# Octaplexerv6.net
KiCad netlist of a schematic drawn in EAGLE
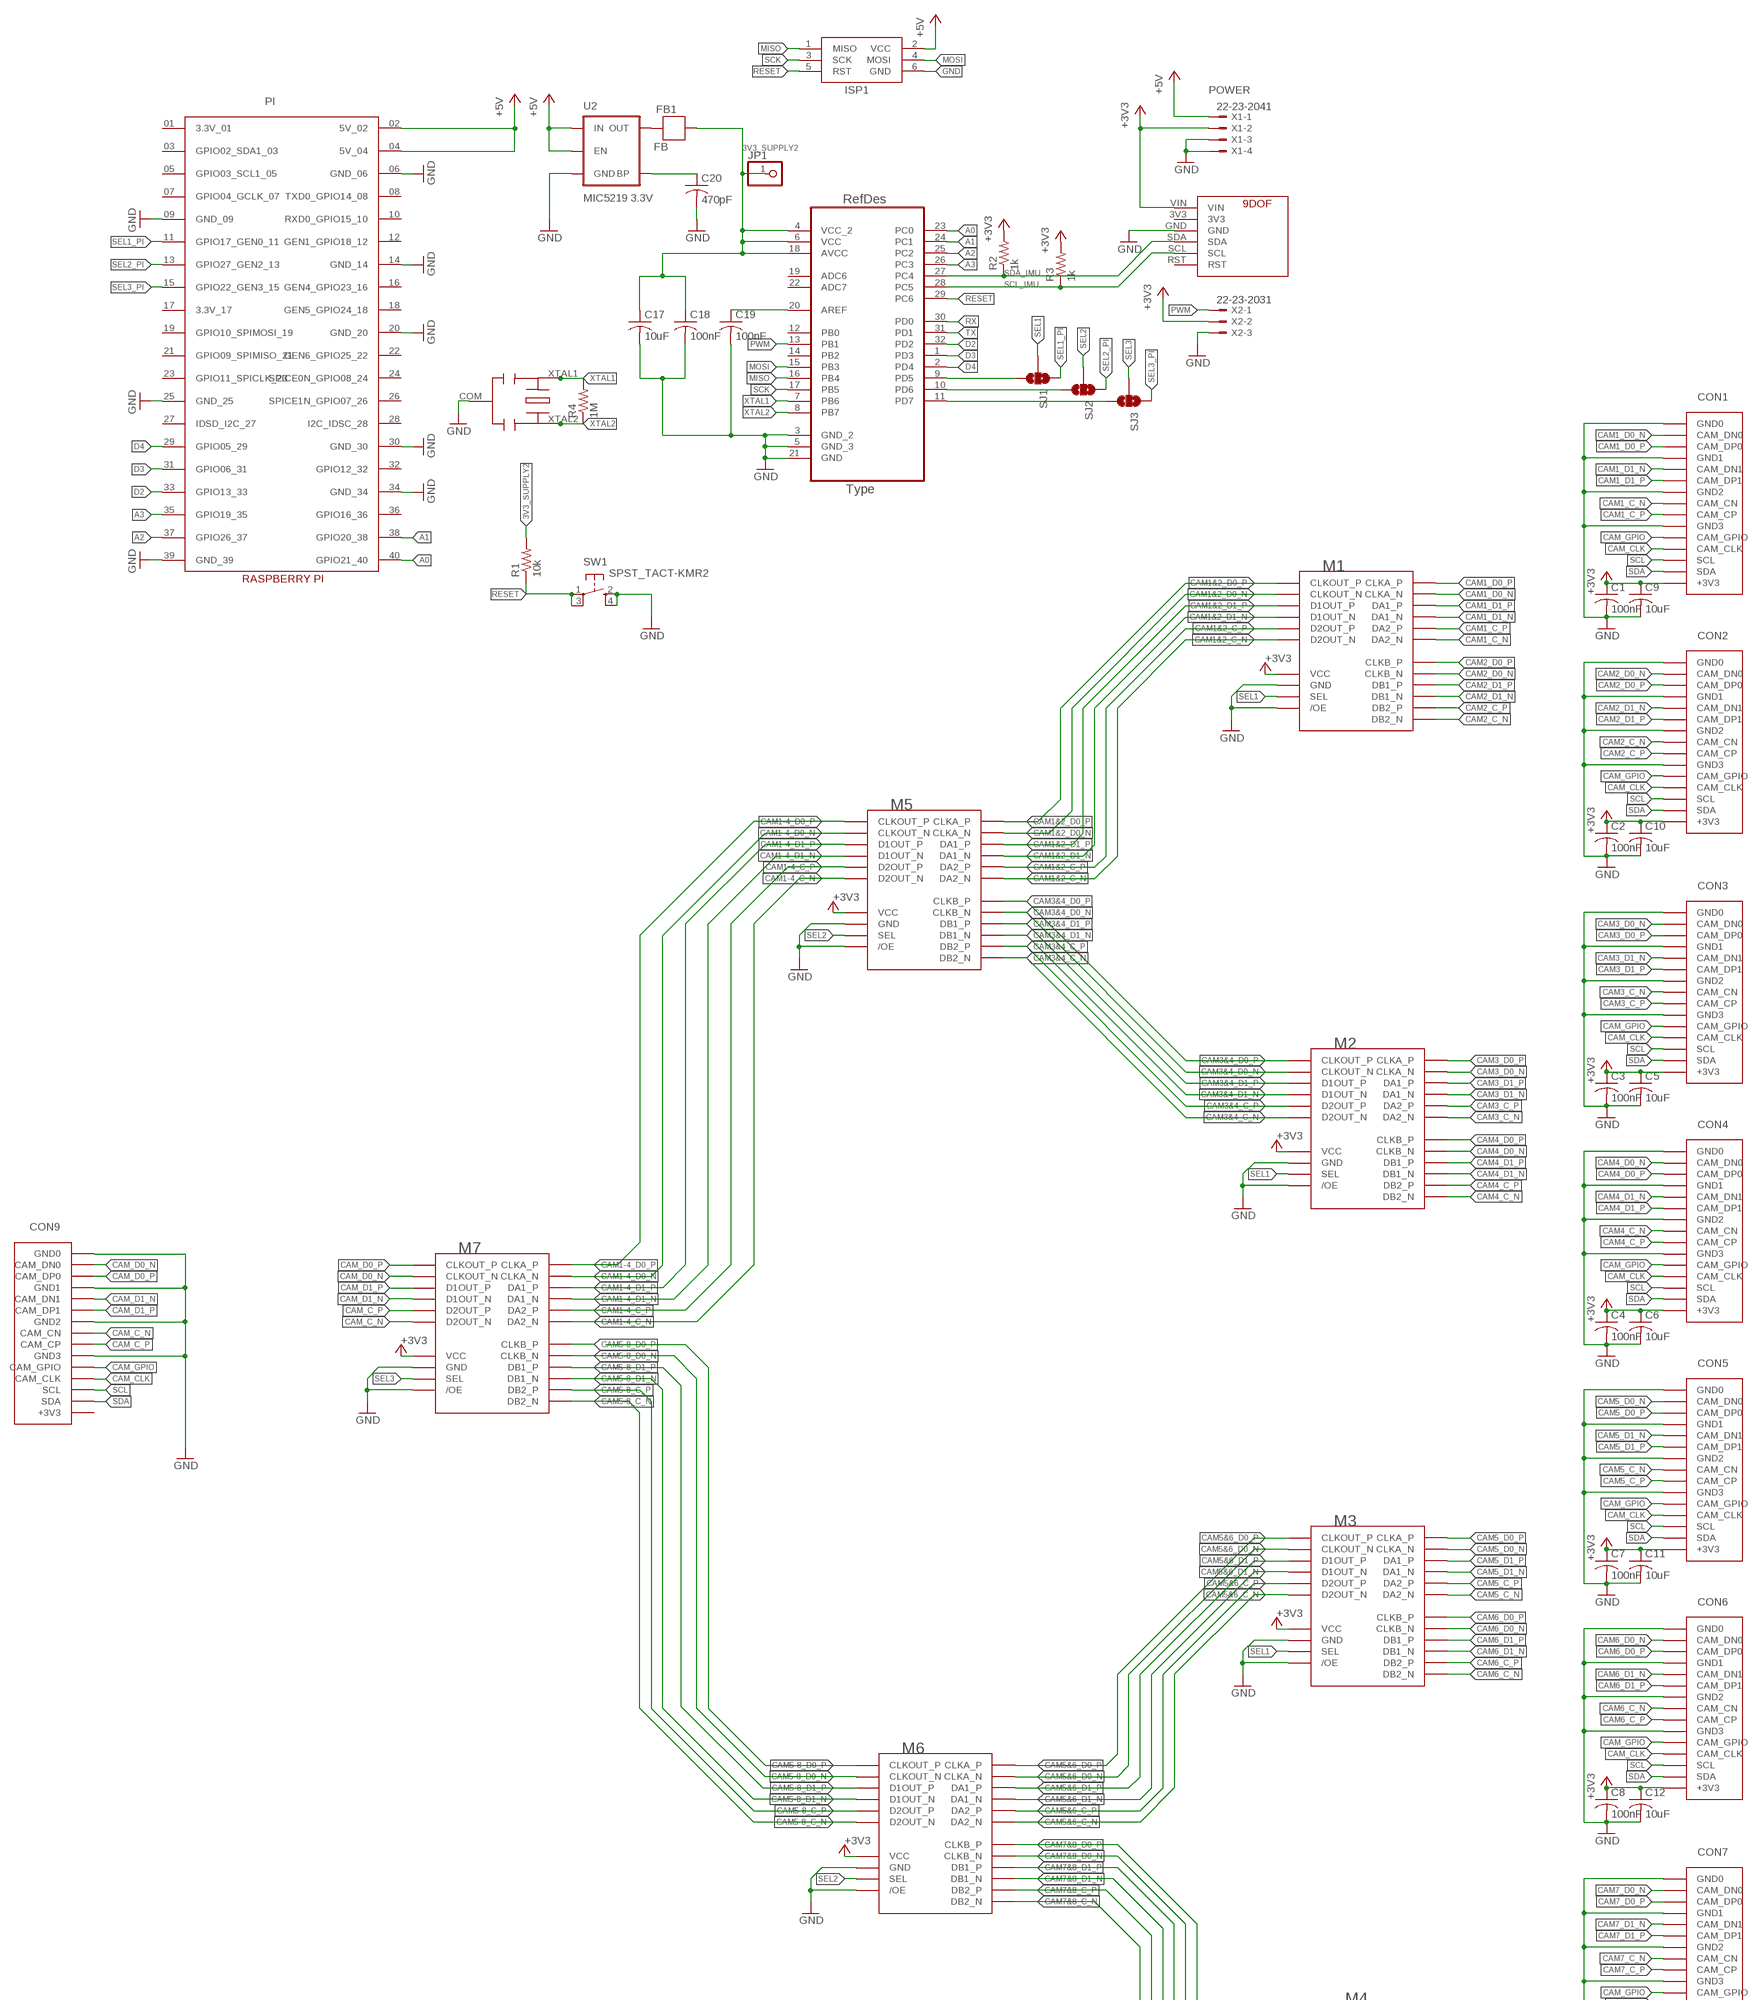
[diagram p0: schematic, sheet 1, part 1 of 2]
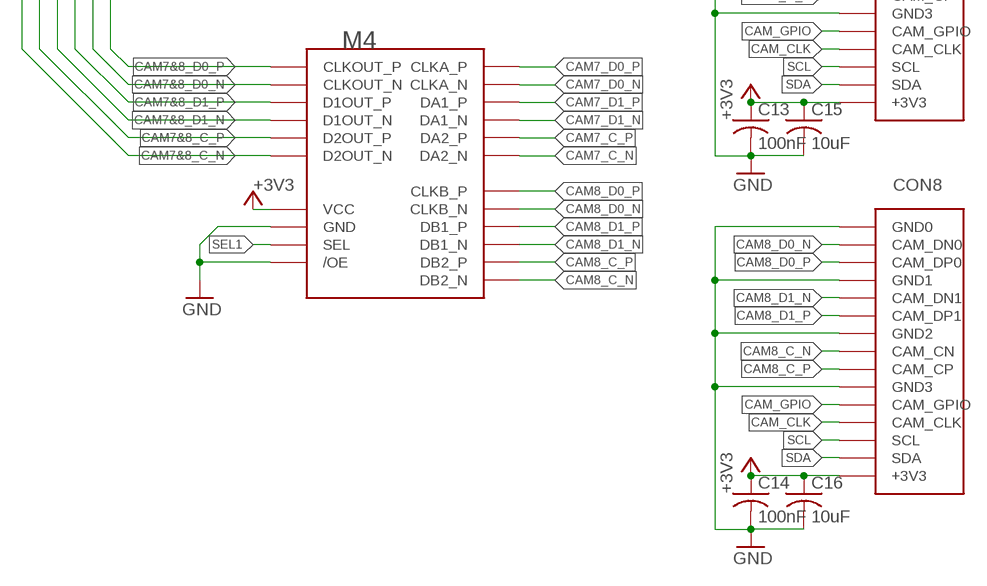
[diagram p1: schematic, sheet 1, part 2 of 2]

(export (version "E")
  (design (tool "Eeschema 10.0.6"))
  (components
    (comp (ref "328P")
      (value "ATMEGA328P-AU")
      (footprint "eagle-import:QFP80P900X900X120-32N")
      (libsource (lib "eagle-import") (part "ATMEGA328P-AU"))
    )
    (comp (ref "C1")
      (value "100nF")
      (footprint "eagle-import:C0603")
      (libsource (lib "eagle-import") (part "C-USC0603"))
    )
    (comp (ref "C2")
      (value "100nF")
      (footprint "eagle-import:C0603")
      (libsource (lib "eagle-import") (part "C-USC0603"))
    )
    (comp (ref "C3")
      (value "100nF")
      (footprint "eagle-import:C0603")
      (libsource (lib "eagle-import") (part "C-USC0603"))
    )
    (comp (ref "C4")
      (value "100nF")
      (footprint "eagle-import:C0603")
      (libsource (lib "eagle-import") (part "C-USC0603"))
    )
    (comp (ref "C5")
      (value "10uF")
      (footprint "eagle-import:C0603")
      (libsource (lib "eagle-import") (part "C-USC0603"))
    )
    (comp (ref "C6")
      (value "10uF")
      (footprint "eagle-import:C0603")
      (libsource (lib "eagle-import") (part "C-USC0603"))
    )
    (comp (ref "C7")
      (value "100nF")
      (footprint "eagle-import:C0603")
      (libsource (lib "eagle-import") (part "C-USC0603"))
    )
    (comp (ref "C8")
      (value "100nF")
      (footprint "eagle-import:C0603")
      (libsource (lib "eagle-import") (part "C-USC0603"))
    )
    (comp (ref "C9")
      (value "10uF")
      (footprint "eagle-import:C0603")
      (libsource (lib "eagle-import") (part "C-USC0603"))
    )
    (comp (ref "C10")
      (value "10uF")
      (footprint "eagle-import:C0603")
      (libsource (lib "eagle-import") (part "C-USC0603"))
    )
    (comp (ref "C11")
      (value "10uF")
      (footprint "eagle-import:C0603")
      (libsource (lib "eagle-import") (part "C-USC0603"))
    )
    (comp (ref "C12")
      (value "10uF")
      (footprint "eagle-import:C0603")
      (libsource (lib "eagle-import") (part "C-USC0603"))
    )
    (comp (ref "C13")
      (value "100nF")
      (footprint "eagle-import:C0603")
      (libsource (lib "eagle-import") (part "C-USC0603"))
    )
    (comp (ref "C14")
      (value "100nF")
      (footprint "eagle-import:C0603")
      (libsource (lib "eagle-import") (part "C-USC0603"))
    )
    (comp (ref "C15")
      (value "10uF")
      (footprint "eagle-import:C0603")
      (libsource (lib "eagle-import") (part "C-USC0603"))
    )
    (comp (ref "C16")
      (value "10uF")
      (footprint "eagle-import:C0603")
      (libsource (lib "eagle-import") (part "C-USC0603"))
    )
    (comp (ref "C17")
      (value "10uF")
      (footprint "eagle-import:C0603")
      (libsource (lib "eagle-import") (part "C-USC0603"))
    )
    (comp (ref "C18")
      (value "100nF")
      (footprint "eagle-import:C0603")
      (libsource (lib "eagle-import") (part "C-USC0603"))
    )
    (comp (ref "C19")
      (value "100nF")
      (footprint "eagle-import:C0603")
      (libsource (lib "eagle-import") (part "C-USC0603"))
    )
    (comp (ref "C20")
      (value "470pF")
      (footprint "eagle-import:C0603")
      (libsource (lib "eagle-import") (part "C-USC0603"))
    )
    (comp (ref "CON1")
      (value "SLW15S-1C7LF")
      (footprint "eagle-import:SLW15R-1C7LF")
      (libsource (lib "eagle-import") (part "SLW15S-1C7LF"))
    )
    (comp (ref "CON2")
      (value "SLW15S-1C7LF")
      (footprint "eagle-import:SLW15R-1C7LF")
      (libsource (lib "eagle-import") (part "SLW15S-1C7LF"))
    )
    (comp (ref "CON3")
      (value "SLW15S-1C7LF")
      (footprint "eagle-import:SLW15R-1C7LF")
      (libsource (lib "eagle-import") (part "SLW15S-1C7LF"))
    )
    (comp (ref "CON4")
      (value "SLW15S-1C7LF")
      (footprint "eagle-import:SLW15R-1C7LF")
      (libsource (lib "eagle-import") (part "SLW15S-1C7LF"))
    )
    (comp (ref "CON5")
      (value "SLW15S-1C7LF")
      (footprint "eagle-import:SLW15R-1C7LF")
      (libsource (lib "eagle-import") (part "SLW15S-1C7LF"))
    )
    (comp (ref "CON6")
      (value "SLW15S-1C7LF")
      (footprint "eagle-import:SLW15R-1C7LF")
      (libsource (lib "eagle-import") (part "SLW15S-1C7LF"))
    )
    (comp (ref "CON7")
      (value "SLW15S-1C7LF")
      (footprint "eagle-import:SLW15R-1C7LF")
      (libsource (lib "eagle-import") (part "SLW15S-1C7LF"))
    )
    (comp (ref "CON8")
      (value "SLW15S-1C7LF")
      (footprint "eagle-import:SLW15R-1C7LF")
      (libsource (lib "eagle-import") (part "SLW15S-1C7LF"))
    )
    (comp (ref "CON9")
      (value "SLW15S-1C7LF")
      (footprint "eagle-import:SLW15R-1C7LF")
      (libsource (lib "eagle-import") (part "SLW15S-1C7LF"))
    )
    (comp (ref "FB1")
      (value "FB")
      (footprint "eagle-import:0603")
      (libsource (lib "eagle-import") (part "FB"))
    )
    (comp (ref "ISP1")
      (value "AVRISP-6")
      (footprint "eagle-import:AVRISP")
      (libsource (lib "eagle-import") (part "AVRISP-6"))
    )
    (comp (ref "JP1")
      (value "PINHD-1X1")
      (footprint "eagle-import:1X01")
      (libsource (lib "eagle-import") (part "PINHD-1X1"))
    )
    (comp (ref "M1")
      (value "FSA642")
      (footprint "eagle-import:FSA642")
      (libsource (lib "eagle-import") (part "FSA642"))
    )
    (comp (ref "M2")
      (value "FSA642")
      (footprint "eagle-import:FSA642")
      (libsource (lib "eagle-import") (part "FSA642"))
    )
    (comp (ref "M3")
      (value "FSA642")
      (footprint "eagle-import:FSA642")
      (libsource (lib "eagle-import") (part "FSA642"))
    )
    (comp (ref "M4")
      (value "FSA642")
      (footprint "eagle-import:FSA642")
      (libsource (lib "eagle-import") (part "FSA642"))
    )
    (comp (ref "M5")
      (value "FSA642")
      (footprint "eagle-import:FSA642")
      (libsource (lib "eagle-import") (part "FSA642"))
    )
    (comp (ref "M6")
      (value "FSA642")
      (footprint "eagle-import:FSA642")
      (libsource (lib "eagle-import") (part "FSA642"))
    )
    (comp (ref "M7")
      (value "FSA642")
      (footprint "eagle-import:FSA642")
      (libsource (lib "eagle-import") (part "FSA642"))
    )
    (comp (ref "PI")
      (value "RASPBERRYPI_SHIELD")
      (footprint "eagle-import:RASPBERRYPI_SHIELD")
      (libsource (lib "eagle-import") (part "RASPBERRYPI_SHIELD"))
    )
    (comp (ref "R1")
      (value "10k")
      (footprint "eagle-import:R0603")
      (libsource (lib "eagle-import") (part "R-US_R0603"))
    )
    (comp (ref "R2")
      (value "1k")
      (footprint "eagle-import:R0603")
      (libsource (lib "eagle-import") (part "R-US_R0603"))
    )
    (comp (ref "R3")
      (value "1k")
      (footprint "eagle-import:R0603")
      (libsource (lib "eagle-import") (part "R-US_R0603"))
    )
    (comp (ref "R4")
      (value "1M")
      (footprint "eagle-import:R0603")
      (libsource (lib "eagle-import") (part "R-US_R0603"))
    )
    (comp (ref "SJ1")
      (value "SOLDERJUMPER_2WAYPASTE2&3")
      (footprint "eagle-import:SJ_3_PASTE2&3")
      (libsource (lib "eagle-import") (part "SOLDERJUMPER_2WAYPASTE2&3"))
    )
    (comp (ref "SJ2")
      (value "SOLDERJUMPER_2WAYPASTE2&3")
      (footprint "eagle-import:SJ_3_PASTE2&3")
      (libsource (lib "eagle-import") (part "SOLDERJUMPER_2WAYPASTE2&3"))
    )
    (comp (ref "SJ3")
      (value "SOLDERJUMPER_2WAYPASTE2&3")
      (footprint "eagle-import:SJ_3_PASTE2&3")
      (libsource (lib "eagle-import") (part "SOLDERJUMPER_2WAYPASTE2&3"))
    )
    (comp (ref "SW1")
      (value "SPST_TACT-KMR2")
      (footprint "eagle-import:KMR2")
      (libsource (lib "eagle-import") (part "SPST_TACT-KMR2"))
    )
    (comp (ref "U$1")
      (value "RESONATOR-PRQC")
      (footprint "eagle-import:PRQC")
      (libsource (lib "eagle-import") (part "RESONATOR-PRQC"))
    )
    (comp (ref "U$2")
      (value "9DOF-BNO055")
      (footprint "eagle-import:9DOF_FLAT")
      (libsource (lib "eagle-import") (part "9DOF-BNO055"))
    )
    (comp (ref "U2")
      (value "MIC5219 3.3V")
      (footprint "eagle-import:SOT23-5")
      (libsource (lib "eagle-import") (part "V_REG_MIC52193.3V"))
    )
    (comp (ref "X1")
      (value "22-23-2041")
      (footprint "eagle-import:22-23-2041")
      (fields (field (name "MF") "MOLEX"))
      (libsource (lib "eagle-import") (part "22-23-2041"))
    )
    (comp (ref "X2")
      (value "22-23-2031")
      (footprint "eagle-import:22-23-2031")
      (fields (field (name "MF") "MOLEX"))
      (libsource (lib "eagle-import") (part "22-23-2031"))
    )
  )
  (nets
    (net (code "1") (name "+3V3") (class "Default")
      (node (ref "C1") (pin "1") (pinfunction "1_1") (pintype "passive"))
      (node (ref "C10") (pin "1") (pinfunction "1_1") (pintype "passive"))
      (node (ref "C11") (pin "1") (pinfunction "1_1") (pintype "passive"))
      (node (ref "C12") (pin "1") (pinfunction "1_1") (pintype "passive"))
      (node (ref "C13") (pin "1") (pinfunction "1_1") (pintype "passive"))
      (node (ref "C14") (pin "1") (pinfunction "1_1") (pintype "passive"))
      (node (ref "C15") (pin "1") (pinfunction "1_1") (pintype "passive"))
      (node (ref "C16") (pin "1") (pinfunction "1_1") (pintype "passive"))
      (node (ref "C2") (pin "1") (pinfunction "1_1") (pintype "passive"))
      (node (ref "C3") (pin "1") (pinfunction "1_1") (pintype "passive"))
      (node (ref "C4") (pin "1") (pinfunction "1_1") (pintype "passive"))
      (node (ref "C5") (pin "1") (pinfunction "1_1") (pintype "passive"))
      (node (ref "C6") (pin "1") (pinfunction "1_1") (pintype "passive"))
      (node (ref "C7") (pin "1") (pinfunction "1_1") (pintype "passive"))
      (node (ref "C8") (pin "1") (pinfunction "1_1") (pintype "passive"))
      (node (ref "C9") (pin "1") (pinfunction "1_1") (pintype "passive"))
      (node (ref "CON1") (pin "3.3V") (pinfunction "+3V3_3.3V") (pintype "bidirectional"))
      (node (ref "CON2") (pin "3.3V") (pinfunction "+3V3_3.3V") (pintype "bidirectional"))
      (node (ref "CON3") (pin "3.3V") (pinfunction "+3V3_3.3V") (pintype "bidirectional"))
      (node (ref "CON4") (pin "3.3V") (pinfunction "+3V3_3.3V") (pintype "bidirectional"))
      (node (ref "CON5") (pin "3.3V") (pinfunction "+3V3_3.3V") (pintype "bidirectional"))
      (node (ref "CON6") (pin "3.3V") (pinfunction "+3V3_3.3V") (pintype "bidirectional"))
      (node (ref "CON7") (pin "3.3V") (pinfunction "+3V3_3.3V") (pintype "bidirectional"))
      (node (ref "CON8") (pin "3.3V") (pinfunction "+3V3_3.3V") (pintype "bidirectional"))
      (node (ref "M1") (pin "VCC") (pinfunction "VCC_VCC") (pintype "bidirectional"))
      (node (ref "M2") (pin "VCC") (pinfunction "VCC_VCC") (pintype "bidirectional"))
      (node (ref "M3") (pin "VCC") (pinfunction "VCC_VCC") (pintype "bidirectional"))
      (node (ref "M4") (pin "VCC") (pinfunction "VCC_VCC") (pintype "bidirectional"))
      (node (ref "M5") (pin "VCC") (pinfunction "VCC_VCC") (pintype "bidirectional"))
      (node (ref "M6") (pin "VCC") (pinfunction "VCC_VCC") (pintype "bidirectional"))
      (node (ref "M7") (pin "VCC") (pinfunction "VCC_VCC") (pintype "bidirectional"))
      (node (ref "R2") (pin "2") (pinfunction "2_2") (pintype "passive"))
      (node (ref "R3") (pin "2") (pinfunction "2_2") (pintype "passive"))
      (node (ref "U$2") (pin "VIN") (pinfunction "VIN_VIN") (pintype "bidirectional"))
      (node (ref "X1") (pin "2") (pinfunction "S_2") (pintype "passive"))
      (node (ref "X2") (pin "2") (pinfunction "S_2") (pintype "passive"))
    )
    (net (code "2") (name "+5V") (class "Default")
      (node (ref "ISP1") (pin "2") (pinfunction "VCC_2") (pintype "power_in"))
      (node (ref "PI") (pin "02") (pinfunction "5V_02_02") (pintype "bidirectional"))
      (node (ref "PI") (pin "04") (pinfunction "5V_04_04") (pintype "bidirectional"))
      (node (ref "U2") (pin "1") (pinfunction "IN_1") (pintype "input"))
      (node (ref "U2") (pin "3") (pinfunction "EN_3") (pintype "input"))
      (node (ref "X1") (pin "1") (pinfunction "S_1") (pintype "passive"))
    )
    (net (code "3") (name "/SCL_IMU") (class "Default")
      (node (ref "328P") (pin "28") (pinfunction "PC5_28") (pintype "bidirectional"))
      (node (ref "R3") (pin "1") (pinfunction "1_1") (pintype "passive"))
      (node (ref "U$2") (pin "SCL") (pinfunction "SCL_SCL") (pintype "bidirectional"))
    )
    (net (code "4") (name "/SDA_IMU") (class "Default")
      (node (ref "328P") (pin "27") (pinfunction "PC4_27") (pintype "bidirectional"))
      (node (ref "R2") (pin "1") (pinfunction "1_1") (pintype "passive"))
      (node (ref "U$2") (pin "SDA") (pinfunction "SDA_SDA") (pintype "bidirectional"))
    )
    (net (code "5") (name "3V3_SUPPLY2") (class "Default")
      (node (ref "328P") (pin "18") (pinfunction "AVCC_18") (pintype "power_in"))
      (node (ref "328P") (pin "4") (pinfunction "VCC_2_4") (pintype "power_in"))
      (node (ref "328P") (pin "6") (pinfunction "VCC_6") (pintype "power_in"))
      (node (ref "C17") (pin "1") (pinfunction "1_1") (pintype "passive"))
      (node (ref "C18") (pin "1") (pinfunction "1_1") (pintype "passive"))
      (node (ref "FB1") (pin "1") (pinfunction "P$1_1") (pintype "bidirectional"))
      (node (ref "JP1") (pin "1") (pinfunction "1_1") (pintype "passive"))
      (node (ref "R1") (pin "2") (pinfunction "2_2") (pintype "passive"))
    )
    (net (code "6") (name "A0") (class "Default")
      (node (ref "328P") (pin "23") (pinfunction "PC0_23") (pintype "bidirectional"))
      (node (ref "PI") (pin "40") (pinfunction "GPIO21_40_40") (pintype "bidirectional"))
    )
    (net (code "7") (name "A1") (class "Default")
      (node (ref "328P") (pin "24") (pinfunction "PC1_24") (pintype "bidirectional"))
      (node (ref "PI") (pin "38") (pinfunction "GPIO20_38_38") (pintype "bidirectional"))
    )
    (net (code "8") (name "A2") (class "Default")
      (node (ref "328P") (pin "25") (pinfunction "PC2_25") (pintype "bidirectional"))
      (node (ref "PI") (pin "37") (pinfunction "GPIO26_37_37") (pintype "bidirectional"))
    )
    (net (code "9") (name "A3") (class "Default")
      (node (ref "328P") (pin "26") (pinfunction "PC3_26") (pintype "bidirectional"))
      (node (ref "PI") (pin "35") (pinfunction "GPIO19_35_35") (pintype "bidirectional"))
    )
    (net (code "10") (name "CAM1&2_C_N") (class "Default")
      (node (ref "M1") (pin "D2N") (pinfunction "D2OUT_N_D2N") (pintype "bidirectional"))
      (node (ref "M5") (pin "DA2N") (pinfunction "DA2_N_DA2N") (pintype "bidirectional"))
    )
    (net (code "11") (name "CAM1&2_C_P") (class "Default")
      (node (ref "M1") (pin "D2P") (pinfunction "D2OUT_P_D2P") (pintype "bidirectional"))
      (node (ref "M5") (pin "DA2P") (pinfunction "DA2_P_DA2P") (pintype "bidirectional"))
    )
    (net (code "12") (name "CAM1&2_D0_N") (class "Default")
      (node (ref "M1") (pin "CLKN") (pinfunction "CLKOUT_N_CLKN") (pintype "bidirectional"))
      (node (ref "M5") (pin "CLKAN") (pinfunction "CLKA_N_CLKAN") (pintype "bidirectional"))
    )
    (net (code "13") (name "CAM1&2_D0_P") (class "Default")
      (node (ref "M1") (pin "CLKP") (pinfunction "CLKOUT_P_CLKP") (pintype "bidirectional"))
      (node (ref "M5") (pin "CLKAP") (pinfunction "CLKA_P_CLKAP") (pintype "bidirectional"))
    )
    (net (code "14") (name "CAM1&2_D1_N") (class "Default")
      (node (ref "M1") (pin "D1N") (pinfunction "D1OUT_N_D1N") (pintype "bidirectional"))
      (node (ref "M5") (pin "DA1N") (pinfunction "DA1_N_DA1N") (pintype "bidirectional"))
    )
    (net (code "15") (name "CAM1&2_D1_P") (class "Default")
      (node (ref "M1") (pin "D1P") (pinfunction "D1OUT_P_D1P") (pintype "bidirectional"))
      (node (ref "M5") (pin "DA1P") (pinfunction "DA1_P_DA1P") (pintype "bidirectional"))
    )
    (net (code "16") (name "CAM1-4_C_N") (class "Default")
      (node (ref "M5") (pin "D2N") (pinfunction "D2OUT_N_D2N") (pintype "bidirectional"))
      (node (ref "M7") (pin "DA2N") (pinfunction "DA2_N_DA2N") (pintype "bidirectional"))
    )
    (net (code "17") (name "CAM1-4_C_P") (class "Default")
      (node (ref "M5") (pin "D2P") (pinfunction "D2OUT_P_D2P") (pintype "bidirectional"))
      (node (ref "M7") (pin "DA2P") (pinfunction "DA2_P_DA2P") (pintype "bidirectional"))
    )
    (net (code "18") (name "CAM1-4_D0_N") (class "Default")
      (node (ref "M5") (pin "CLKN") (pinfunction "CLKOUT_N_CLKN") (pintype "bidirectional"))
      (node (ref "M7") (pin "CLKAN") (pinfunction "CLKA_N_CLKAN") (pintype "bidirectional"))
    )
    (net (code "19") (name "CAM1-4_D0_P") (class "Default")
      (node (ref "M5") (pin "CLKP") (pinfunction "CLKOUT_P_CLKP") (pintype "bidirectional"))
      (node (ref "M7") (pin "CLKAP") (pinfunction "CLKA_P_CLKAP") (pintype "bidirectional"))
    )
    (net (code "20") (name "CAM1-4_D1_N") (class "Default")
      (node (ref "M5") (pin "D1N") (pinfunction "D1OUT_N_D1N") (pintype "bidirectional"))
      (node (ref "M7") (pin "DA1N") (pinfunction "DA1_N_DA1N") (pintype "bidirectional"))
    )
    (net (code "21") (name "CAM1-4_D1_P") (class "Default")
      (node (ref "M5") (pin "D1P") (pinfunction "D1OUT_P_D1P") (pintype "bidirectional"))
      (node (ref "M7") (pin "DA1P") (pinfunction "DA1_P_DA1P") (pintype "bidirectional"))
    )
    (net (code "22") (name "CAM1_C_N") (class "Default")
      (node (ref "CON1") (pin "CAM_C_N") (pinfunction "CAM_CN_CAM_C_N") (pintype "bidirectional"))
      (node (ref "M1") (pin "DA2N") (pinfunction "DA2_N_DA2N") (pintype "bidirectional"))
    )
    (net (code "23") (name "CAM1_C_P") (class "Default")
      (node (ref "CON1") (pin "CAM_C_P") (pinfunction "CAM_CP_CAM_C_P") (pintype "bidirectional"))
      (node (ref "M1") (pin "DA2P") (pinfunction "DA2_P_DA2P") (pintype "bidirectional"))
    )
    (net (code "24") (name "CAM1_D0_N") (class "Default")
      (node (ref "CON1") (pin "CAM_D0_N") (pinfunction "CAM_DN0_CAM_D0_N") (pintype "bidirectional"))
      (node (ref "M1") (pin "CLKAN") (pinfunction "CLKA_N_CLKAN") (pintype "bidirectional"))
    )
    (net (code "25") (name "CAM1_D0_P") (class "Default")
      (node (ref "CON1") (pin "CAM_D0_P") (pinfunction "CAM_DP0_CAM_D0_P") (pintype "bidirectional"))
      (node (ref "M1") (pin "CLKAP") (pinfunction "CLKA_P_CLKAP") (pintype "bidirectional"))
    )
    (net (code "26") (name "CAM1_D1_N") (class "Default")
      (node (ref "CON1") (pin "CAM_D1_N") (pinfunction "CAM_DN1_CAM_D1_N") (pintype "bidirectional"))
      (node (ref "M1") (pin "DA1N") (pinfunction "DA1_N_DA1N") (pintype "bidirectional"))
    )
    (net (code "27") (name "CAM1_D1_P") (class "Default")
      (node (ref "CON1") (pin "CAM_D1_P") (pinfunction "CAM_DP1_CAM_D1_P") (pintype "bidirectional"))
      (node (ref "M1") (pin "DA1P") (pinfunction "DA1_P_DA1P") (pintype "bidirectional"))
    )
    (net (code "28") (name "CAM2_C_N") (class "Default")
      (node (ref "CON2") (pin "CAM_C_N") (pinfunction "CAM_CN_CAM_C_N") (pintype "bidirectional"))
      (node (ref "M1") (pin "DB2N") (pinfunction "DB2_N_DB2N") (pintype "bidirectional"))
    )
    (net (code "29") (name "CAM2_C_P") (class "Default")
      (node (ref "CON2") (pin "CAM_C_P") (pinfunction "CAM_CP_CAM_C_P") (pintype "bidirectional"))
      (node (ref "M1") (pin "DB2P") (pinfunction "DB2_P_DB2P") (pintype "bidirectional"))
    )
    (net (code "30") (name "CAM2_D0_N") (class "Default")
      (node (ref "CON2") (pin "CAM_D0_N") (pinfunction "CAM_DN0_CAM_D0_N") (pintype "bidirectional"))
      (node (ref "M1") (pin "CLKBN") (pinfunction "CLKB_N_CLKBN") (pintype "bidirectional"))
    )
    (net (code "31") (name "CAM2_D0_P") (class "Default")
      (node (ref "CON2") (pin "CAM_D0_P") (pinfunction "CAM_DP0_CAM_D0_P") (pintype "bidirectional"))
      (node (ref "M1") (pin "CLKBP") (pinfunction "CLKB_P_CLKBP") (pintype "bidirectional"))
    )
    (net (code "32") (name "CAM2_D1_N") (class "Default")
      (node (ref "CON2") (pin "CAM_D1_N") (pinfunction "CAM_DN1_CAM_D1_N") (pintype "bidirectional"))
      (node (ref "M1") (pin "DB1N") (pinfunction "DB1_N_DB1N") (pintype "bidirectional"))
    )
    (net (code "33") (name "CAM2_D1_P") (class "Default")
      (node (ref "CON2") (pin "CAM_D1_P") (pinfunction "CAM_DP1_CAM_D1_P") (pintype "bidirectional"))
      (node (ref "M1") (pin "DB1P") (pinfunction "DB1_P_DB1P") (pintype "bidirectional"))
    )
    (net (code "34") (name "CAM3&4_C_N") (class "Default")
      (node (ref "M2") (pin "D2N") (pinfunction "D2OUT_N_D2N") (pintype "bidirectional"))
      (node (ref "M5") (pin "DB2N") (pinfunction "DB2_N_DB2N") (pintype "bidirectional"))
    )
    (net (code "35") (name "CAM3&4_C_P") (class "Default")
      (node (ref "M2") (pin "D2P") (pinfunction "D2OUT_P_D2P") (pintype "bidirectional"))
      (node (ref "M5") (pin "DB2P") (pinfunction "DB2_P_DB2P") (pintype "bidirectional"))
    )
    (net (code "36") (name "CAM3&4_D0_N") (class "Default")
      (node (ref "M2") (pin "CLKN") (pinfunction "CLKOUT_N_CLKN") (pintype "bidirectional"))
      (node (ref "M5") (pin "CLKBN") (pinfunction "CLKB_N_CLKBN") (pintype "bidirectional"))
    )
    (net (code "37") (name "CAM3&4_D0_P") (class "Default")
      (node (ref "M2") (pin "CLKP") (pinfunction "CLKOUT_P_CLKP") (pintype "bidirectional"))
      (node (ref "M5") (pin "CLKBP") (pinfunction "CLKB_P_CLKBP") (pintype "bidirectional"))
    )
    (net (code "38") (name "CAM3&4_D1_N") (class "Default")
      (node (ref "M2") (pin "D1N") (pinfunction "D1OUT_N_D1N") (pintype "bidirectional"))
      (node (ref "M5") (pin "DB1N") (pinfunction "DB1_N_DB1N") (pintype "bidirectional"))
    )
    (net (code "39") (name "CAM3&4_D1_P") (class "Default")
      (node (ref "M2") (pin "D1P") (pinfunction "D1OUT_P_D1P") (pintype "bidirectional"))
      (node (ref "M5") (pin "DB1P") (pinfunction "DB1_P_DB1P") (pintype "bidirectional"))
    )
    (net (code "40") (name "CAM3_C_N") (class "Default")
      (node (ref "CON3") (pin "CAM_C_N") (pinfunction "CAM_CN_CAM_C_N") (pintype "bidirectional"))
      (node (ref "M2") (pin "DA2N") (pinfunction "DA2_N_DA2N") (pintype "bidirectional"))
    )
    (net (code "41") (name "CAM3_C_P") (class "Default")
      (node (ref "CON3") (pin "CAM_C_P") (pinfunction "CAM_CP_CAM_C_P") (pintype "bidirectional"))
      (node (ref "M2") (pin "DA2P") (pinfunction "DA2_P_DA2P") (pintype "bidirectional"))
    )
    (net (code "42") (name "CAM3_D0_N") (class "Default")
      (node (ref "CON3") (pin "CAM_D0_N") (pinfunction "CAM_DN0_CAM_D0_N") (pintype "bidirectional"))
      (node (ref "M2") (pin "CLKAN") (pinfunction "CLKA_N_CLKAN") (pintype "bidirectional"))
    )
    (net (code "43") (name "CAM3_D0_P") (class "Default")
      (node (ref "CON3") (pin "CAM_D0_P") (pinfunction "CAM_DP0_CAM_D0_P") (pintype "bidirectional"))
      (node (ref "M2") (pin "CLKAP") (pinfunction "CLKA_P_CLKAP") (pintype "bidirectional"))
    )
    (net (code "44") (name "CAM3_D1_N") (class "Default")
      (node (ref "CON3") (pin "CAM_D1_N") (pinfunction "CAM_DN1_CAM_D1_N") (pintype "bidirectional"))
      (node (ref "M2") (pin "DA1N") (pinfunction "DA1_N_DA1N") (pintype "bidirectional"))
    )
    (net (code "45") (name "CAM3_D1_P") (class "Default")
      (node (ref "CON3") (pin "CAM_D1_P") (pinfunction "CAM_DP1_CAM_D1_P") (pintype "bidirectional"))
      (node (ref "M2") (pin "DA1P") (pinfunction "DA1_P_DA1P") (pintype "bidirectional"))
    )
    (net (code "46") (name "CAM4_C_N") (class "Default")
      (node (ref "CON4") (pin "CAM_C_N") (pinfunction "CAM_CN_CAM_C_N") (pintype "bidirectional"))
      (node (ref "M2") (pin "DB2N") (pinfunction "DB2_N_DB2N") (pintype "bidirectional"))
    )
    (net (code "47") (name "CAM4_C_P") (class "Default")
      (node (ref "CON4") (pin "CAM_C_P") (pinfunction "CAM_CP_CAM_C_P") (pintype "bidirectional"))
      (node (ref "M2") (pin "DB2P") (pinfunction "DB2_P_DB2P") (pintype "bidirectional"))
    )
    (net (code "48") (name "CAM4_D0_N") (class "Default")
      (node (ref "CON4") (pin "CAM_D0_N") (pinfunction "CAM_DN0_CAM_D0_N") (pintype "bidirectional"))
      (node (ref "M2") (pin "CLKBN") (pinfunction "CLKB_N_CLKBN") (pintype "bidirectional"))
    )
    (net (code "49") (name "CAM4_D0_P") (class "Default")
      (node (ref "CON4") (pin "CAM_D0_P") (pinfunction "CAM_DP0_CAM_D0_P") (pintype "bidirectional"))
      (node (ref "M2") (pin "CLKBP") (pinfunction "CLKB_P_CLKBP") (pintype "bidirectional"))
    )
    (net (code "50") (name "CAM4_D1_N") (class "Default")
      (node (ref "CON4") (pin "CAM_D1_N") (pinfunction "CAM_DN1_CAM_D1_N") (pintype "bidirectional"))
      (node (ref "M2") (pin "DB1N") (pinfunction "DB1_N_DB1N") (pintype "bidirectional"))
    )
    (net (code "51") (name "CAM4_D1_P") (class "Default")
      (node (ref "CON4") (pin "CAM_D1_P") (pinfunction "CAM_DP1_CAM_D1_P") (pintype "bidirectional"))
      (node (ref "M2") (pin "DB1P") (pinfunction "DB1_P_DB1P") (pintype "bidirectional"))
    )
    (net (code "52") (name "CAM5&6_C_N") (class "Default")
      (node (ref "M3") (pin "D2N") (pinfunction "D2OUT_N_D2N") (pintype "bidirectional"))
      (node (ref "M6") (pin "DA2N") (pinfunction "DA2_N_DA2N") (pintype "bidirectional"))
    )
    (net (code "53") (name "CAM5&6_C_P") (class "Default")
      (node (ref "M3") (pin "D2P") (pinfunction "D2OUT_P_D2P") (pintype "bidirectional"))
      (node (ref "M6") (pin "DA2P") (pinfunction "DA2_P_DA2P") (pintype "bidirectional"))
    )
    (net (code "54") (name "CAM5&6_D0_N") (class "Default")
      (node (ref "M3") (pin "CLKN") (pinfunction "CLKOUT_N_CLKN") (pintype "bidirectional"))
      (node (ref "M6") (pin "CLKAN") (pinfunction "CLKA_N_CLKAN") (pintype "bidirectional"))
    )
    (net (code "55") (name "CAM5&6_D0_P") (class "Default")
      (node (ref "M3") (pin "CLKP") (pinfunction "CLKOUT_P_CLKP") (pintype "bidirectional"))
      (node (ref "M6") (pin "CLKAP") (pinfunction "CLKA_P_CLKAP") (pintype "bidirectional"))
    )
    (net (code "56") (name "CAM5&6_D1_N") (class "Default")
      (node (ref "M3") (pin "D1N") (pinfunction "D1OUT_N_D1N") (pintype "bidirectional"))
      (node (ref "M6") (pin "DA1N") (pinfunction "DA1_N_DA1N") (pintype "bidirectional"))
    )
    (net (code "57") (name "CAM5&6_D1_P") (class "Default")
      (node (ref "M3") (pin "D1P") (pinfunction "D1OUT_P_D1P") (pintype "bidirectional"))
      (node (ref "M6") (pin "DA1P") (pinfunction "DA1_P_DA1P") (pintype "bidirectional"))
    )
    (net (code "58") (name "CAM5-8_C_N") (class "Default")
      (node (ref "M6") (pin "D2N") (pinfunction "D2OUT_N_D2N") (pintype "bidirectional"))
      (node (ref "M7") (pin "DB2N") (pinfunction "DB2_N_DB2N") (pintype "bidirectional"))
    )
    (net (code "59") (name "CAM5-8_C_P") (class "Default")
      (node (ref "M6") (pin "D2P") (pinfunction "D2OUT_P_D2P") (pintype "bidirectional"))
      (node (ref "M7") (pin "DB2P") (pinfunction "DB2_P_DB2P") (pintype "bidirectional"))
    )
    (net (code "60") (name "CAM5-8_D0_N") (class "Default")
      (node (ref "M6") (pin "CLKN") (pinfunction "CLKOUT_N_CLKN") (pintype "bidirectional"))
      (node (ref "M7") (pin "CLKBN") (pinfunction "CLKB_N_CLKBN") (pintype "bidirectional"))
    )
    (net (code "61") (name "CAM5-8_D0_P") (class "Default")
      (node (ref "M6") (pin "CLKP") (pinfunction "CLKOUT_P_CLKP") (pintype "bidirectional"))
      (node (ref "M7") (pin "CLKBP") (pinfunction "CLKB_P_CLKBP") (pintype "bidirectional"))
    )
    (net (code "62") (name "CAM5-8_D1_N") (class "Default")
      (node (ref "M6") (pin "D1N") (pinfunction "D1OUT_N_D1N") (pintype "bidirectional"))
      (node (ref "M7") (pin "DB1N") (pinfunction "DB1_N_DB1N") (pintype "bidirectional"))
    )
    (net (code "63") (name "CAM5-8_D1_P") (class "Default")
      (node (ref "M6") (pin "D1P") (pinfunction "D1OUT_P_D1P") (pintype "bidirectional"))
      (node (ref "M7") (pin "DB1P") (pinfunction "DB1_P_DB1P") (pintype "bidirectional"))
    )
    (net (code "64") (name "CAM5_C_N") (class "Default")
      (node (ref "CON5") (pin "CAM_C_N") (pinfunction "CAM_CN_CAM_C_N") (pintype "bidirectional"))
      (node (ref "M3") (pin "DA2N") (pinfunction "DA2_N_DA2N") (pintype "bidirectional"))
    )
    (net (code "65") (name "CAM5_C_P") (class "Default")
      (node (ref "CON5") (pin "CAM_C_P") (pinfunction "CAM_CP_CAM_C_P") (pintype "bidirectional"))
      (node (ref "M3") (pin "DA2P") (pinfunction "DA2_P_DA2P") (pintype "bidirectional"))
    )
    (net (code "66") (name "CAM5_D0_N") (class "Default")
      (node (ref "CON5") (pin "CAM_D0_N") (pinfunction "CAM_DN0_CAM_D0_N") (pintype "bidirectional"))
      (node (ref "M3") (pin "CLKAN") (pinfunction "CLKA_N_CLKAN") (pintype "bidirectional"))
    )
    (net (code "67") (name "CAM5_D0_P") (class "Default")
      (node (ref "CON5") (pin "CAM_D0_P") (pinfunction "CAM_DP0_CAM_D0_P") (pintype "bidirectional"))
      (node (ref "M3") (pin "CLKAP") (pinfunction "CLKA_P_CLKAP") (pintype "bidirectional"))
    )
    (net (code "68") (name "CAM5_D1_N") (class "Default")
      (node (ref "CON5") (pin "CAM_D1_N") (pinfunction "CAM_DN1_CAM_D1_N") (pintype "bidirectional"))
      (node (ref "M3") (pin "DA1N") (pinfunction "DA1_N_DA1N") (pintype "bidirectional"))
    )
    (net (code "69") (name "CAM5_D1_P") (class "Default")
      (node (ref "CON5") (pin "CAM_D1_P") (pinfunction "CAM_DP1_CAM_D1_P") (pintype "bidirectional"))
      (node (ref "M3") (pin "DA1P") (pinfunction "DA1_P_DA1P") (pintype "bidirectional"))
    )
    (net (code "70") (name "CAM6_C_N") (class "Default")
      (node (ref "CON6") (pin "CAM_C_N") (pinfunction "CAM_CN_CAM_C_N") (pintype "bidirectional"))
      (node (ref "M3") (pin "DB2N") (pinfunction "DB2_N_DB2N") (pintype "bidirectional"))
    )
    (net (code "71") (name "CAM6_C_P") (class "Default")
      (node (ref "CON6") (pin "CAM_C_P") (pinfunction "CAM_CP_CAM_C_P") (pintype "bidirectional"))
      (node (ref "M3") (pin "DB2P") (pinfunction "DB2_P_DB2P") (pintype "bidirectional"))
    )
    (net (code "72") (name "CAM6_D0_N") (class "Default")
      (node (ref "CON6") (pin "CAM_D0_N") (pinfunction "CAM_DN0_CAM_D0_N") (pintype "bidirectional"))
      (node (ref "M3") (pin "CLKBN") (pinfunction "CLKB_N_CLKBN") (pintype "bidirectional"))
    )
    (net (code "73") (name "CAM6_D0_P") (class "Default")
      (node (ref "CON6") (pin "CAM_D0_P") (pinfunction "CAM_DP0_CAM_D0_P") (pintype "bidirectional"))
      (node (ref "M3") (pin "CLKBP") (pinfunction "CLKB_P_CLKBP") (pintype "bidirectional"))
    )
    (net (code "74") (name "CAM6_D1_N") (class "Default")
      (node (ref "CON6") (pin "CAM_D1_N") (pinfunction "CAM_DN1_CAM_D1_N") (pintype "bidirectional"))
      (node (ref "M3") (pin "DB1N") (pinfunction "DB1_N_DB1N") (pintype "bidirectional"))
    )
    (net (code "75") (name "CAM6_D1_P") (class "Default")
      (node (ref "CON6") (pin "CAM_D1_P") (pinfunction "CAM_DP1_CAM_D1_P") (pintype "bidirectional"))
      (node (ref "M3") (pin "DB1P") (pinfunction "DB1_P_DB1P") (pintype "bidirectional"))
    )
    (net (code "76") (name "CAM7&8_C_N") (class "Default")
      (node (ref "M4") (pin "D2N") (pinfunction "D2OUT_N_D2N") (pintype "bidirectional"))
      (node (ref "M6") (pin "DB2N") (pinfunction "DB2_N_DB2N") (pintype "bidirectional"))
    )
    (net (code "77") (name "CAM7&8_C_P") (class "Default")
      (node (ref "M4") (pin "D2P") (pinfunction "D2OUT_P_D2P") (pintype "bidirectional"))
      (node (ref "M6") (pin "DB2P") (pinfunction "DB2_P_DB2P") (pintype "bidirectional"))
    )
    (net (code "78") (name "CAM7&8_D0_N") (class "Default")
      (node (ref "M4") (pin "CLKN") (pinfunction "CLKOUT_N_CLKN") (pintype "bidirectional"))
      (node (ref "M6") (pin "CLKBN") (pinfunction "CLKB_N_CLKBN") (pintype "bidirectional"))
    )
    (net (code "79") (name "CAM7&8_D0_P") (class "Default")
      (node (ref "M4") (pin "CLKP") (pinfunction "CLKOUT_P_CLKP") (pintype "bidirectional"))
      (node (ref "M6") (pin "CLKBP") (pinfunction "CLKB_P_CLKBP") (pintype "bidirectional"))
    )
    (net (code "80") (name "CAM7&8_D1_N") (class "Default")
      (node (ref "M4") (pin "D1N") (pinfunction "D1OUT_N_D1N") (pintype "bidirectional"))
      (node (ref "M6") (pin "DB1N") (pinfunction "DB1_N_DB1N") (pintype "bidirectional"))
    )
    (net (code "81") (name "CAM7&8_D1_P") (class "Default")
      (node (ref "M4") (pin "D1P") (pinfunction "D1OUT_P_D1P") (pintype "bidirectional"))
      (node (ref "M6") (pin "DB1P") (pinfunction "DB1_P_DB1P") (pintype "bidirectional"))
    )
    (net (code "82") (name "CAM7_C_N") (class "Default")
      (node (ref "CON7") (pin "CAM_C_N") (pinfunction "CAM_CN_CAM_C_N") (pintype "bidirectional"))
      (node (ref "M4") (pin "DA2N") (pinfunction "DA2_N_DA2N") (pintype "bidirectional"))
    )
    (net (code "83") (name "CAM7_C_P") (class "Default")
      (node (ref "CON7") (pin "CAM_C_P") (pinfunction "CAM_CP_CAM_C_P") (pintype "bidirectional"))
      (node (ref "M4") (pin "DA2P") (pinfunction "DA2_P_DA2P") (pintype "bidirectional"))
    )
    (net (code "84") (name "CAM7_D0_N") (class "Default")
      (node (ref "CON7") (pin "CAM_D0_N") (pinfunction "CAM_DN0_CAM_D0_N") (pintype "bidirectional"))
      (node (ref "M4") (pin "CLKAN") (pinfunction "CLKA_N_CLKAN") (pintype "bidirectional"))
    )
    (net (code "85") (name "CAM7_D0_P") (class "Default")
      (node (ref "CON7") (pin "CAM_D0_P") (pinfunction "CAM_DP0_CAM_D0_P") (pintype "bidirectional"))
      (node (ref "M4") (pin "CLKAP") (pinfunction "CLKA_P_CLKAP") (pintype "bidirectional"))
    )
    (net (code "86") (name "CAM7_D1_N") (class "Default")
      (node (ref "CON7") (pin "CAM_D1_N") (pinfunction "CAM_DN1_CAM_D1_N") (pintype "bidirectional"))
      (node (ref "M4") (pin "DA1N") (pinfunction "DA1_N_DA1N") (pintype "bidirectional"))
    )
    (net (code "87") (name "CAM7_D1_P") (class "Default")
      (node (ref "CON7") (pin "CAM_D1_P") (pinfunction "CAM_DP1_CAM_D1_P") (pintype "bidirectional"))
      (node (ref "M4") (pin "DA1P") (pinfunction "DA1_P_DA1P") (pintype "bidirectional"))
    )
    (net (code "88") (name "CAM8_C_N") (class "Default")
      (node (ref "CON8") (pin "CAM_C_N") (pinfunction "CAM_CN_CAM_C_N") (pintype "bidirectional"))
      (node (ref "M4") (pin "DB2N") (pinfunction "DB2_N_DB2N") (pintype "bidirectional"))
    )
    (net (code "89") (name "CAM8_C_P") (class "Default")
      (node (ref "CON8") (pin "CAM_C_P") (pinfunction "CAM_CP_CAM_C_P") (pintype "bidirectional"))
      (node (ref "M4") (pin "DB2P") (pinfunction "DB2_P_DB2P") (pintype "bidirectional"))
    )
    (net (code "90") (name "CAM8_D0_N") (class "Default")
      (node (ref "CON8") (pin "CAM_D0_N") (pinfunction "CAM_DN0_CAM_D0_N") (pintype "bidirectional"))
      (node (ref "M4") (pin "CLKBN") (pinfunction "CLKB_N_CLKBN") (pintype "bidirectional"))
    )
    (net (code "91") (name "CAM8_D0_P") (class "Default")
      (node (ref "CON8") (pin "CAM_D0_P") (pinfunction "CAM_DP0_CAM_D0_P") (pintype "bidirectional"))
      (node (ref "M4") (pin "CLKBP") (pinfunction "CLKB_P_CLKBP") (pintype "bidirectional"))
    )
    (net (code "92") (name "CAM8_D1_N") (class "Default")
      (node (ref "CON8") (pin "CAM_D1_N") (pinfunction "CAM_DN1_CAM_D1_N") (pintype "bidirectional"))
      (node (ref "M4") (pin "DB1N") (pinfunction "DB1_N_DB1N") (pintype "bidirectional"))
    )
    (net (code "93") (name "CAM8_D1_P") (class "Default")
      (node (ref "CON8") (pin "CAM_D1_P") (pinfunction "CAM_DP1_CAM_D1_P") (pintype "bidirectional"))
      (node (ref "M4") (pin "DB1P") (pinfunction "DB1_P_DB1P") (pintype "bidirectional"))
    )
    (net (code "94") (name "CAM_CLK") (class "Default")
      (node (ref "CON1") (pin "CAM_CLK") (pinfunction "CAM_CLK_CAM_CLK") (pintype "bidirectional"))
      (node (ref "CON2") (pin "CAM_CLK") (pinfunction "CAM_CLK_CAM_CLK") (pintype "bidirectional"))
      (node (ref "CON3") (pin "CAM_CLK") (pinfunction "CAM_CLK_CAM_CLK") (pintype "bidirectional"))
      (node (ref "CON4") (pin "CAM_CLK") (pinfunction "CAM_CLK_CAM_CLK") (pintype "bidirectional"))
      (node (ref "CON5") (pin "CAM_CLK") (pinfunction "CAM_CLK_CAM_CLK") (pintype "bidirectional"))
      (node (ref "CON6") (pin "CAM_CLK") (pinfunction "CAM_CLK_CAM_CLK") (pintype "bidirectional"))
      (node (ref "CON7") (pin "CAM_CLK") (pinfunction "CAM_CLK_CAM_CLK") (pintype "bidirectional"))
      (node (ref "CON8") (pin "CAM_CLK") (pinfunction "CAM_CLK_CAM_CLK") (pintype "bidirectional"))
      (node (ref "CON9") (pin "CAM_CLK") (pinfunction "CAM_CLK_CAM_CLK") (pintype "bidirectional"))
    )
    (net (code "95") (name "CAM_C_N") (class "Default")
      (node (ref "CON9") (pin "CAM_C_N") (pinfunction "CAM_CN_CAM_C_N") (pintype "bidirectional"))
      (node (ref "M7") (pin "D2N") (pinfunction "D2OUT_N_D2N") (pintype "bidirectional"))
    )
    (net (code "96") (name "CAM_C_P") (class "Default")
      (node (ref "CON9") (pin "CAM_C_P") (pinfunction "CAM_CP_CAM_C_P") (pintype "bidirectional"))
      (node (ref "M7") (pin "D2P") (pinfunction "D2OUT_P_D2P") (pintype "bidirectional"))
    )
    (net (code "97") (name "CAM_D0_N") (class "Default")
      (node (ref "CON9") (pin "CAM_D0_N") (pinfunction "CAM_DN0_CAM_D0_N") (pintype "bidirectional"))
      (node (ref "M7") (pin "CLKN") (pinfunction "CLKOUT_N_CLKN") (pintype "bidirectional"))
    )
    (net (code "98") (name "CAM_D0_P") (class "Default")
      (node (ref "CON9") (pin "CAM_D0_P") (pinfunction "CAM_DP0_CAM_D0_P") (pintype "bidirectional"))
      (node (ref "M7") (pin "CLKP") (pinfunction "CLKOUT_P_CLKP") (pintype "bidirectional"))
    )
    (net (code "99") (name "CAM_D1_N") (class "Default")
      (node (ref "CON9") (pin "CAM_D1_N") (pinfunction "CAM_DN1_CAM_D1_N") (pintype "bidirectional"))
      (node (ref "M7") (pin "D1N") (pinfunction "D1OUT_N_D1N") (pintype "bidirectional"))
    )
    (net (code "100") (name "CAM_D1_P") (class "Default")
      (node (ref "CON9") (pin "CAM_D1_P") (pinfunction "CAM_DP1_CAM_D1_P") (pintype "bidirectional"))
      (node (ref "M7") (pin "D1P") (pinfunction "D1OUT_P_D1P") (pintype "bidirectional"))
    )
    (net (code "101") (name "CAM_GPIO") (class "Default")
      (node (ref "CON1") (pin "CAM_GPIO") (pinfunction "CAM_GPIO_CAM_GPIO") (pintype "bidirectional"))
      (node (ref "CON2") (pin "CAM_GPIO") (pinfunction "CAM_GPIO_CAM_GPIO") (pintype "bidirectional"))
      (node (ref "CON3") (pin "CAM_GPIO") (pinfunction "CAM_GPIO_CAM_GPIO") (pintype "bidirectional"))
      (node (ref "CON4") (pin "CAM_GPIO") (pinfunction "CAM_GPIO_CAM_GPIO") (pintype "bidirectional"))
      (node (ref "CON5") (pin "CAM_GPIO") (pinfunction "CAM_GPIO_CAM_GPIO") (pintype "bidirectional"))
      (node (ref "CON6") (pin "CAM_GPIO") (pinfunction "CAM_GPIO_CAM_GPIO") (pintype "bidirectional"))
      (node (ref "CON7") (pin "CAM_GPIO") (pinfunction "CAM_GPIO_CAM_GPIO") (pintype "bidirectional"))
      (node (ref "CON8") (pin "CAM_GPIO") (pinfunction "CAM_GPIO_CAM_GPIO") (pintype "bidirectional"))
      (node (ref "CON9") (pin "CAM_GPIO") (pinfunction "CAM_GPIO_CAM_GPIO") (pintype "bidirectional"))
    )
    (net (code "102") (name "D2") (class "Default")
      (node (ref "328P") (pin "32") (pinfunction "PD2_32") (pintype "bidirectional"))
      (node (ref "PI") (pin "33") (pinfunction "GPIO13_33_33") (pintype "bidirectional"))
    )
    (net (code "103") (name "D3") (class "Default")
      (node (ref "328P") (pin "1") (pinfunction "PD3_1") (pintype "bidirectional"))
      (node (ref "PI") (pin "31") (pinfunction "GPIO06_31_31") (pintype "bidirectional"))
    )
    (net (code "104") (name "D4") (class "Default")
      (node (ref "328P") (pin "2") (pinfunction "PD4_2") (pintype "bidirectional"))
      (node (ref "PI") (pin "29") (pinfunction "GPIO05_29_29") (pintype "bidirectional"))
    )
    (net (code "105") (name "GND") (class "Default")
      (node (ref "328P") (pin "21") (pinfunction "GND_21") (pintype "passive"))
      (node (ref "328P") (pin "3") (pinfunction "GND_2_3") (pintype "passive"))
      (node (ref "328P") (pin "5") (pinfunction "GND_3_5") (pintype "passive"))
      (node (ref "C1") (pin "2") (pinfunction "2_2") (pintype "passive"))
      (node (ref "C10") (pin "2") (pinfunction "2_2") (pintype "passive"))
      (node (ref "C11") (pin "2") (pinfunction "2_2") (pintype "passive"))
      (node (ref "C12") (pin "2") (pinfunction "2_2") (pintype "passive"))
      (node (ref "C13") (pin "2") (pinfunction "2_2") (pintype "passive"))
      (node (ref "C14") (pin "2") (pinfunction "2_2") (pintype "passive"))
      (node (ref "C15") (pin "2") (pinfunction "2_2") (pintype "passive"))
      (node (ref "C16") (pin "2") (pinfunction "2_2") (pintype "passive"))
      (node (ref "C17") (pin "2") (pinfunction "2_2") (pintype "passive"))
      (node (ref "C18") (pin "2") (pinfunction "2_2") (pintype "passive"))
      (node (ref "C19") (pin "2") (pinfunction "2_2") (pintype "passive"))
      (node (ref "C2") (pin "2") (pinfunction "2_2") (pintype "passive"))
      (node (ref "C20") (pin "2") (pinfunction "2_2") (pintype "passive"))
      (node (ref "C3") (pin "2") (pinfunction "2_2") (pintype "passive"))
      (node (ref "C4") (pin "2") (pinfunction "2_2") (pintype "passive"))
      (node (ref "C5") (pin "2") (pinfunction "2_2") (pintype "passive"))
      (node (ref "C6") (pin "2") (pinfunction "2_2") (pintype "passive"))
      (node (ref "C7") (pin "2") (pinfunction "2_2") (pintype "passive"))
      (node (ref "C8") (pin "2") (pinfunction "2_2") (pintype "passive"))
      (node (ref "C9") (pin "2") (pinfunction "2_2") (pintype "passive"))
      (node (ref "CON1") (pin "GND") (pinfunction "GND0_GND") (pintype "bidirectional"))
      (node (ref "CON1") (pin "GND1") (pinfunction "GND1_GND1") (pintype "bidirectional"))
      (node (ref "CON1") (pin "GND2") (pinfunction "GND2_GND2") (pintype "bidirectional"))
      (node (ref "CON1") (pin "GND3") (pinfunction "GND3_GND3") (pintype "bidirectional"))
      (node (ref "CON2") (pin "GND") (pinfunction "GND0_GND") (pintype "bidirectional"))
      (node (ref "CON2") (pin "GND1") (pinfunction "GND1_GND1") (pintype "bidirectional"))
      (node (ref "CON2") (pin "GND2") (pinfunction "GND2_GND2") (pintype "bidirectional"))
      (node (ref "CON2") (pin "GND3") (pinfunction "GND3_GND3") (pintype "bidirectional"))
      (node (ref "CON3") (pin "GND") (pinfunction "GND0_GND") (pintype "bidirectional"))
      (node (ref "CON3") (pin "GND1") (pinfunction "GND1_GND1") (pintype "bidirectional"))
      (node (ref "CON3") (pin "GND2") (pinfunction "GND2_GND2") (pintype "bidirectional"))
      (node (ref "CON3") (pin "GND3") (pinfunction "GND3_GND3") (pintype "bidirectional"))
      (node (ref "CON4") (pin "GND") (pinfunction "GND0_GND") (pintype "bidirectional"))
      (node (ref "CON4") (pin "GND1") (pinfunction "GND1_GND1") (pintype "bidirectional"))
      (node (ref "CON4") (pin "GND2") (pinfunction "GND2_GND2") (pintype "bidirectional"))
      (node (ref "CON4") (pin "GND3") (pinfunction "GND3_GND3") (pintype "bidirectional"))
      (node (ref "CON5") (pin "GND") (pinfunction "GND0_GND") (pintype "bidirectional"))
      (node (ref "CON5") (pin "GND1") (pinfunction "GND1_GND1") (pintype "bidirectional"))
      (node (ref "CON5") (pin "GND2") (pinfunction "GND2_GND2") (pintype "bidirectional"))
      (node (ref "CON5") (pin "GND3") (pinfunction "GND3_GND3") (pintype "bidirectional"))
      (node (ref "CON6") (pin "GND") (pinfunction "GND0_GND") (pintype "bidirectional"))
      (node (ref "CON6") (pin "GND1") (pinfunction "GND1_GND1") (pintype "bidirectional"))
      (node (ref "CON6") (pin "GND2") (pinfunction "GND2_GND2") (pintype "bidirectional"))
      (node (ref "CON6") (pin "GND3") (pinfunction "GND3_GND3") (pintype "bidirectional"))
      (node (ref "CON7") (pin "GND") (pinfunction "GND0_GND") (pintype "bidirectional"))
      (node (ref "CON7") (pin "GND1") (pinfunction "GND1_GND1") (pintype "bidirectional"))
      (node (ref "CON7") (pin "GND2") (pinfunction "GND2_GND2") (pintype "bidirectional"))
      (node (ref "CON7") (pin "GND3") (pinfunction "GND3_GND3") (pintype "bidirectional"))
      (node (ref "CON8") (pin "GND") (pinfunction "GND0_GND") (pintype "bidirectional"))
      (node (ref "CON8") (pin "GND1") (pinfunction "GND1_GND1") (pintype "bidirectional"))
      (node (ref "CON8") (pin "GND2") (pinfunction "GND2_GND2") (pintype "bidirectional"))
      (node (ref "CON8") (pin "GND3") (pinfunction "GND3_GND3") (pintype "bidirectional"))
      (node (ref "CON9") (pin "GND") (pinfunction "GND0_GND") (pintype "bidirectional"))
      (node (ref "CON9") (pin "GND1") (pinfunction "GND1_GND1") (pintype "bidirectional"))
      (node (ref "CON9") (pin "GND2") (pinfunction "GND2_GND2") (pintype "bidirectional"))
      (node (ref "CON9") (pin "GND3") (pinfunction "GND3_GND3") (pintype "bidirectional"))
      (node (ref "ISP1") (pin "6") (pinfunction "GND_6") (pintype "power_in"))
      (node (ref "M1") (pin "/OE") (pinfunction "/OE_/OE") (pintype "bidirectional"))
      (node (ref "M1") (pin "GND") (pinfunction "GND_GND") (pintype "bidirectional"))
      (node (ref "M2") (pin "/OE") (pinfunction "/OE_/OE") (pintype "bidirectional"))
      (node (ref "M2") (pin "GND") (pinfunction "GND_GND") (pintype "bidirectional"))
      (node (ref "M3") (pin "/OE") (pinfunction "/OE_/OE") (pintype "bidirectional"))
      (node (ref "M3") (pin "GND") (pinfunction "GND_GND") (pintype "bidirectional"))
      (node (ref "M4") (pin "/OE") (pinfunction "/OE_/OE") (pintype "bidirectional"))
      (node (ref "M4") (pin "GND") (pinfunction "GND_GND") (pintype "bidirectional"))
      (node (ref "M5") (pin "/OE") (pinfunction "/OE_/OE") (pintype "bidirectional"))
      (node (ref "M5") (pin "GND") (pinfunction "GND_GND") (pintype "bidirectional"))
      (node (ref "M6") (pin "/OE") (pinfunction "/OE_/OE") (pintype "bidirectional"))
      (node (ref "M6") (pin "GND") (pinfunction "GND_GND") (pintype "bidirectional"))
      (node (ref "M7") (pin "/OE") (pinfunction "/OE_/OE") (pintype "bidirectional"))
      (node (ref "M7") (pin "GND") (pinfunction "GND_GND") (pintype "bidirectional"))
      (node (ref "PI") (pin "06") (pinfunction "GND_06_06") (pintype "bidirectional"))
      (node (ref "PI") (pin "09") (pinfunction "GND_09_09") (pintype "bidirectional"))
      (node (ref "PI") (pin "14") (pinfunction "GND_14_14") (pintype "bidirectional"))
      (node (ref "PI") (pin "20") (pinfunction "GND_20_20") (pintype "bidirectional"))
      (node (ref "PI") (pin "25") (pinfunction "GND_25_25") (pintype "bidirectional"))
      (node (ref "PI") (pin "30") (pinfunction "GND_30_30") (pintype "bidirectional"))
      (node (ref "PI") (pin "34") (pinfunction "GND_34_34") (pintype "bidirectional"))
      (node (ref "PI") (pin "39") (pinfunction "GND_39_39") (pintype "bidirectional"))
      (node (ref "SW1") (pin "2") (pinfunction "S_2") (pintype "passive"))
      (node (ref "SW1") (pin "4") (pinfunction "S1_4") (pintype "passive"))
      (node (ref "U$1") (pin "COM") (pinfunction "COM_COM") (pintype "bidirectional"))
      (node (ref "U$2") (pin "GND") (pinfunction "GND_GND") (pintype "bidirectional"))
      (node (ref "U2") (pin "2") (pinfunction "GND_2") (pintype "input"))
      (node (ref "X1") (pin "3") (pinfunction "S_3") (pintype "passive"))
      (node (ref "X1") (pin "4") (pinfunction "S_4") (pintype "passive"))
      (node (ref "X2") (pin "3") (pinfunction "S_3") (pintype "passive"))
    )
    (net (code "106") (name "MISO") (class "Default")
      (node (ref "328P") (pin "16") (pinfunction "PB4_16") (pintype "bidirectional"))
      (node (ref "ISP1") (pin "1") (pinfunction "MISO_1") (pintype "input"))
    )
    (net (code "107") (name "MOSI") (class "Default")
      (node (ref "328P") (pin "15") (pinfunction "PB3_15") (pintype "bidirectional"))
      (node (ref "ISP1") (pin "4") (pinfunction "MOSI_4") (pintype "output"))
    )
    (net (code "108") (name "Net-(328P-AREF)") (class "Default")
      (node (ref "328P") (pin "20") (pinfunction "AREF_20") (pintype "input"))
      (node (ref "C19") (pin "1") (pinfunction "1_1") (pintype "passive"))
    )
    (net (code "109") (name "Net-(328P-PD5)") (class "Default")
      (node (ref "328P") (pin "9") (pinfunction "PD5_9") (pintype "bidirectional"))
      (node (ref "SJ1") (pin "3") (pinfunction "3_3") (pintype "passive"))
    )
    (net (code "110") (name "Net-(328P-PD6)") (class "Default")
      (node (ref "328P") (pin "10") (pinfunction "PD6_10") (pintype "bidirectional"))
      (node (ref "SJ2") (pin "3") (pinfunction "3_3") (pintype "passive"))
    )
    (net (code "111") (name "Net-(328P-PD7)") (class "Default")
      (node (ref "328P") (pin "11") (pinfunction "PD7_11") (pintype "bidirectional"))
      (node (ref "SJ3") (pin "3") (pinfunction "3_3") (pintype "passive"))
    )
    (net (code "112") (name "Net-(FB1-P$2)") (class "Default")
      (node (ref "FB1") (pin "2") (pinfunction "P$2_2") (pintype "bidirectional"))
      (node (ref "U2") (pin "5") (pinfunction "OUT_5") (pintype "passive"))
    )
    (net (code "113") (name "Net-(U2-BP)") (class "Default")
      (node (ref "C20") (pin "1") (pinfunction "1_1") (pintype "passive"))
      (node (ref "U2") (pin "4") (pinfunction "BP_4") (pintype "input"))
    )
    (net (code "114") (name "PWM") (class "Default")
      (node (ref "328P") (pin "13") (pinfunction "PB1_13") (pintype "bidirectional"))
      (node (ref "X2") (pin "1") (pinfunction "S_1") (pintype "passive"))
    )
    (net (code "115") (name "RESET") (class "Default")
      (node (ref "328P") (pin "29") (pinfunction "PC6_29") (pintype "bidirectional"))
      (node (ref "ISP1") (pin "5") (pinfunction "RST_5") (pintype "output"))
      (node (ref "R1") (pin "1") (pinfunction "1_1") (pintype "passive"))
      (node (ref "SW1") (pin "1") (pinfunction "P_1") (pintype "passive"))
      (node (ref "SW1") (pin "3") (pinfunction "P1_3") (pintype "passive"))
    )
    (net (code "116") (name "RX") (class "Default")
      (node (ref "328P") (pin "30") (pinfunction "PD0_30") (pintype "bidirectional"))
    )
    (net (code "117") (name "SCK") (class "Default")
      (node (ref "328P") (pin "17") (pinfunction "PB5_17") (pintype "bidirectional"))
      (node (ref "ISP1") (pin "3") (pinfunction "SCK_3") (pintype "output"))
    )
    (net (code "118") (name "SCL") (class "Default")
      (node (ref "CON1") (pin "SCL") (pinfunction "SCL_SCL") (pintype "bidirectional"))
      (node (ref "CON2") (pin "SCL") (pinfunction "SCL_SCL") (pintype "bidirectional"))
      (node (ref "CON3") (pin "SCL") (pinfunction "SCL_SCL") (pintype "bidirectional"))
      (node (ref "CON4") (pin "SCL") (pinfunction "SCL_SCL") (pintype "bidirectional"))
      (node (ref "CON5") (pin "SCL") (pinfunction "SCL_SCL") (pintype "bidirectional"))
      (node (ref "CON6") (pin "SCL") (pinfunction "SCL_SCL") (pintype "bidirectional"))
      (node (ref "CON7") (pin "SCL") (pinfunction "SCL_SCL") (pintype "bidirectional"))
      (node (ref "CON8") (pin "SCL") (pinfunction "SCL_SCL") (pintype "bidirectional"))
      (node (ref "CON9") (pin "SCL") (pinfunction "SCL_SCL") (pintype "bidirectional"))
    )
    (net (code "119") (name "SDA") (class "Default")
      (node (ref "CON1") (pin "SDA") (pinfunction "SDA_SDA") (pintype "bidirectional"))
      (node (ref "CON2") (pin "SDA") (pinfunction "SDA_SDA") (pintype "bidirectional"))
      (node (ref "CON3") (pin "SDA") (pinfunction "SDA_SDA") (pintype "bidirectional"))
      (node (ref "CON4") (pin "SDA") (pinfunction "SDA_SDA") (pintype "bidirectional"))
      (node (ref "CON5") (pin "SDA") (pinfunction "SDA_SDA") (pintype "bidirectional"))
      (node (ref "CON6") (pin "SDA") (pinfunction "SDA_SDA") (pintype "bidirectional"))
      (node (ref "CON7") (pin "SDA") (pinfunction "SDA_SDA") (pintype "bidirectional"))
      (node (ref "CON8") (pin "SDA") (pinfunction "SDA_SDA") (pintype "bidirectional"))
      (node (ref "CON9") (pin "SDA") (pinfunction "SDA_SDA") (pintype "bidirectional"))
    )
    (net (code "120") (name "SEL1") (class "Default")
      (node (ref "M1") (pin "SEL") (pinfunction "SEL_SEL") (pintype "bidirectional"))
      (node (ref "M2") (pin "SEL") (pinfunction "SEL_SEL") (pintype "bidirectional"))
      (node (ref "M3") (pin "SEL") (pinfunction "SEL_SEL") (pintype "bidirectional"))
      (node (ref "M4") (pin "SEL") (pinfunction "SEL_SEL") (pintype "bidirectional"))
      (node (ref "SJ1") (pin "2") (pinfunction "2_2") (pintype "passive"))
    )
    (net (code "121") (name "SEL1_PI") (class "Default")
      (node (ref "PI") (pin "11") (pinfunction "GPIO17_GEN0_11_11") (pintype "bidirectional"))
      (node (ref "SJ1") (pin "1") (pinfunction "1_1") (pintype "passive"))
    )
    (net (code "122") (name "SEL2") (class "Default")
      (node (ref "M5") (pin "SEL") (pinfunction "SEL_SEL") (pintype "bidirectional"))
      (node (ref "M6") (pin "SEL") (pinfunction "SEL_SEL") (pintype "bidirectional"))
      (node (ref "SJ2") (pin "2") (pinfunction "2_2") (pintype "passive"))
    )
    (net (code "123") (name "SEL2_PI") (class "Default")
      (node (ref "PI") (pin "13") (pinfunction "GPIO27_GEN2_13_13") (pintype "bidirectional"))
      (node (ref "SJ2") (pin "1") (pinfunction "1_1") (pintype "passive"))
    )
    (net (code "124") (name "SEL3") (class "Default")
      (node (ref "M7") (pin "SEL") (pinfunction "SEL_SEL") (pintype "bidirectional"))
      (node (ref "SJ3") (pin "2") (pinfunction "2_2") (pintype "passive"))
    )
    (net (code "125") (name "SEL3_PI") (class "Default")
      (node (ref "PI") (pin "15") (pinfunction "GPIO22_GEN3_15_15") (pintype "bidirectional"))
      (node (ref "SJ3") (pin "1") (pinfunction "1_1") (pintype "passive"))
    )
    (net (code "126") (name "TX") (class "Default")
      (node (ref "328P") (pin "31") (pinfunction "PD1_31") (pintype "bidirectional"))
    )
    (net (code "127") (name "XTAL1") (class "Default")
      (node (ref "328P") (pin "7") (pinfunction "PB6_7") (pintype "bidirectional"))
      (node (ref "R4") (pin "2") (pinfunction "2_2") (pintype "passive"))
      (node (ref "U$1") (pin "XTAL1") (pinfunction "XTAL1_XTAL1") (pintype "bidirectional"))
    )
    (net (code "128") (name "XTAL2") (class "Default")
      (node (ref "328P") (pin "8") (pinfunction "PB7_8") (pintype "bidirectional"))
      (node (ref "R4") (pin "1") (pinfunction "1_1") (pintype "passive"))
      (node (ref "U$1") (pin "XTAL2") (pinfunction "XTAL2_XTAL2") (pintype "bidirectional"))
    )
    (net (code "129") (name "unconnected-(328P-ADC6-Pad19)") (class "Default")
      (node (ref "328P") (pin "19") (pinfunction "ADC6_19") (pintype "input"))
    )
    (net (code "130") (name "unconnected-(328P-ADC7-Pad22)") (class "Default")
      (node (ref "328P") (pin "22") (pinfunction "ADC7_22") (pintype "input"))
    )
    (net (code "131") (name "unconnected-(328P-PB0-Pad12)") (class "Default")
      (node (ref "328P") (pin "12") (pinfunction "PB0_12") (pintype "bidirectional"))
    )
    (net (code "132") (name "unconnected-(328P-PB2-Pad14)") (class "Default")
      (node (ref "328P") (pin "14") (pinfunction "PB2_14") (pintype "bidirectional"))
    )
    (net (code "133") (name "unconnected-(CON9-+3V3-Pad3.3V)") (class "Default")
      (node (ref "CON9") (pin "3.3V") (pinfunction "+3V3_3.3V") (pintype "bidirectional"))
    )
    (net (code "134") (name "unconnected-(PI-3.3V_01-Pad01)") (class "Default")
      (node (ref "PI") (pin "01") (pinfunction "3.3V_01_01") (pintype "bidirectional"))
    )
    (net (code "135") (name "unconnected-(PI-3.3V_17-Pad17)") (class "Default")
      (node (ref "PI") (pin "17") (pinfunction "3.3V_17_17") (pintype "bidirectional"))
    )
    (net (code "136") (name "unconnected-(PI-GEN1_GPIO18_12-Pad12)") (class "Default")
      (node (ref "PI") (pin "12") (pinfunction "GEN1_GPIO18_12_12") (pintype "bidirectional"))
    )
    (net (code "137") (name "unconnected-(PI-GEN4_GPIO23_16-Pad16)") (class "Default")
      (node (ref "PI") (pin "16") (pinfunction "GEN4_GPIO23_16_16") (pintype "bidirectional"))
    )
    (net (code "138") (name "unconnected-(PI-GEN5_GPIO24_18-Pad18)") (class "Default")
      (node (ref "PI") (pin "18") (pinfunction "GEN5_GPIO24_18_18") (pintype "bidirectional"))
    )
    (net (code "139") (name "unconnected-(PI-GEN6_GPIO25_22-Pad22)") (class "Default")
      (node (ref "PI") (pin "22") (pinfunction "GEN6_GPIO25_22_22") (pintype "bidirectional"))
    )
    (net (code "140") (name "unconnected-(PI-GPIO02_SDA1_03-Pad03)") (class "Default")
      (node (ref "PI") (pin "03") (pinfunction "GPIO02_SDA1_03_03") (pintype "bidirectional"))
    )
    (net (code "141") (name "unconnected-(PI-GPIO03_SCL1_05-Pad05)") (class "Default")
      (node (ref "PI") (pin "05") (pinfunction "GPIO03_SCL1_05_05") (pintype "bidirectional"))
    )
    (net (code "142") (name "unconnected-(PI-GPIO04_GCLK_07-Pad07)") (class "Default")
      (node (ref "PI") (pin "07") (pinfunction "GPIO04_GCLK_07_07") (pintype "bidirectional"))
    )
    (net (code "143") (name "unconnected-(PI-GPIO09_SPIMISO_21-Pad21)") (class "Default")
      (node (ref "PI") (pin "21") (pinfunction "GPIO09_SPIMISO_21_21") (pintype "bidirectional"))
    )
    (net (code "144") (name "unconnected-(PI-GPIO10_SPIMOSI_19-Pad19)") (class "Default")
      (node (ref "PI") (pin "19") (pinfunction "GPIO10_SPIMOSI_19_19") (pintype "bidirectional"))
    )
    (net (code "145") (name "unconnected-(PI-GPIO11_SPICLK_23-Pad23)") (class "Default")
      (node (ref "PI") (pin "23") (pinfunction "GPIO11_SPICLK_23_23") (pintype "bidirectional"))
    )
    (net (code "146") (name "unconnected-(PI-GPIO12_32-Pad32)") (class "Default")
      (node (ref "PI") (pin "32") (pinfunction "GPIO12_32_32") (pintype "bidirectional"))
    )
    (net (code "147") (name "unconnected-(PI-GPIO16_36-Pad36)") (class "Default")
      (node (ref "PI") (pin "36") (pinfunction "GPIO16_36_36") (pintype "bidirectional"))
    )
    (net (code "148") (name "unconnected-(PI-I2C_IDSC_28-Pad28)") (class "Default")
      (node (ref "PI") (pin "28") (pinfunction "I2C_IDSC_28_28") (pintype "bidirectional"))
    )
    (net (code "149") (name "unconnected-(PI-IDSD_I2C_27-Pad27)") (class "Default")
      (node (ref "PI") (pin "27") (pinfunction "IDSD_I2C_27_27") (pintype "bidirectional"))
    )
    (net (code "150") (name "unconnected-(PI-RXD0_GPIO15_10-Pad10)") (class "Default")
      (node (ref "PI") (pin "10") (pinfunction "RXD0_GPIO15_10_10") (pintype "bidirectional"))
    )
    (net (code "151") (name "unconnected-(PI-SPICE0N_GPIO08_24-Pad24)") (class "Default")
      (node (ref "PI") (pin "24") (pinfunction "SPICE0N_GPIO08_24_24") (pintype "bidirectional"))
    )
    (net (code "152") (name "unconnected-(PI-SPICE1N_GPIO07_26-Pad26)") (class "Default")
      (node (ref "PI") (pin "26") (pinfunction "SPICE1N_GPIO07_26_26") (pintype "bidirectional"))
    )
    (net (code "153") (name "unconnected-(PI-TXD0_GPIO14_08-Pad08)") (class "Default")
      (node (ref "PI") (pin "08") (pinfunction "TXD0_GPIO14_08_08") (pintype "bidirectional"))
    )
    (net (code "154") (name "unconnected-(U$2-Pad3V3)") (class "Default")
      (node (ref "U$2") (pin "3V3") (pinfunction "3V3_3V3") (pintype "bidirectional"))
    )
    (net (code "155") (name "unconnected-(U$2-PadRST)") (class "Default")
      (node (ref "U$2") (pin "RST") (pinfunction "RST_RST") (pintype "bidirectional"))
    )
  )
)
